# Voltage_Regulators.net
KiCad netlist of a schematic drawn in Altium Designer
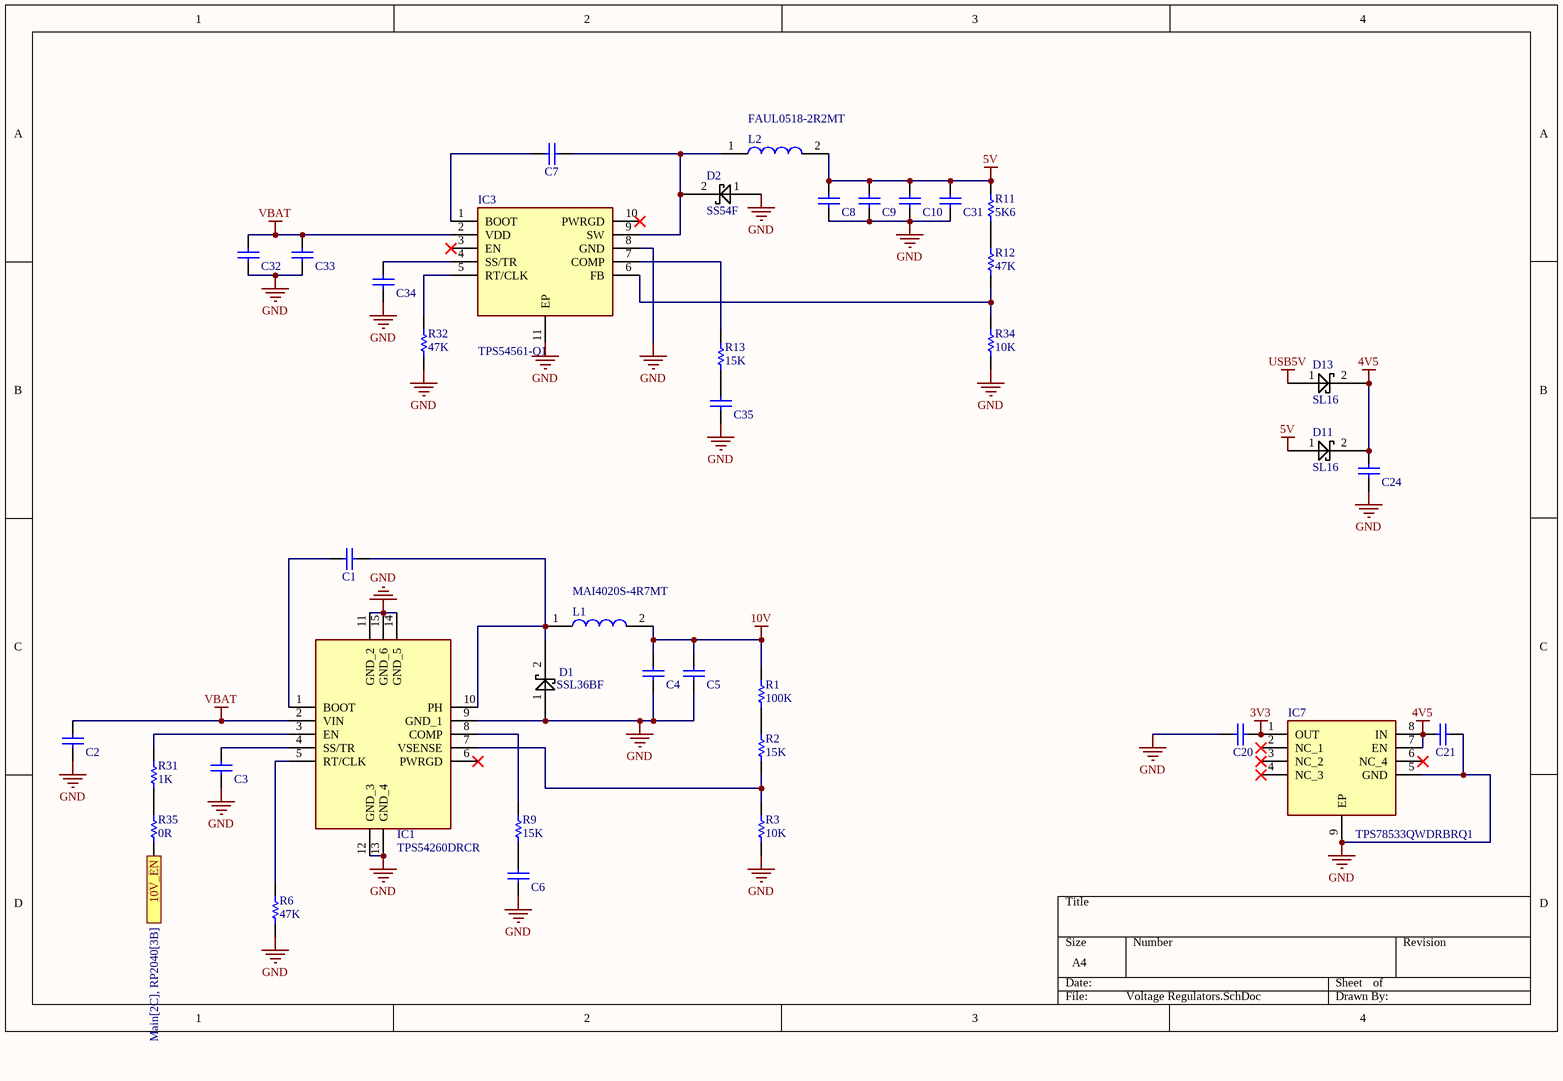
[diagram p0: Voltage Regulators.SchDoc]

(export (version "E")
  (design (tool "Eeschema 10.0.6"))
  (components
    (comp (ref "C1")
      (value "100nF")
      (footprint "WCAP-CSGP_0603_L1.6W0.8H0.8_Reflow")
      (description "WCAP-CSGP Multilayer Ceramic Chip Capacitor, General Purpose, size 0603, X7R, 100nF, 16VDC")
      (fields
        (field (name "MANUFACTURER PART NUMBER") "885012206046")
        (field (name "MANUFACTURER") "Wurth Elektronik")
      )
      (libsource (lib "Altium_WCAP-CSGP (rev22e)") (part "885012206046"))
    )
    (comp (ref "C2")
      (value "3.3µF")
      (footprint "WCAP-CSGP_1206_L3.2W1.6H1.6")
      (description "TDK C3216X7S2A335KT000N\r\n3.3µF MLCC 1206 100V X7S")
      (fields
        (field (name "MANUFACTURER PART NUMBER") "885012208124")
        (field (name "MANUFACTURER") "Wurth Elektronik")
      )
      (libsource (lib "Altium_WCAP-CSGP (rev22e)") (part "885012208124"))
    )
    (comp (ref "C3")
      (value "10nF")
      (footprint "WCAP-CSGP_0603_L1.6W0.8H0.8_Reflow")
      (description "WCAP-CSGP Multilayer Ceramic Chip Capacitor, General Purpose, size 0603, X7R, 10nF, 16VDC")
      (fields
        (field (name "MANUFACTURER PART NUMBER") "885012206040")
        (field (name "MANUFACTURER") "Wurth Elektronik")
      )
      (libsource (lib "Altium_WCAP-CSGP (rev22e)") (part "885012206040"))
    )
    (comp (ref "C4")
      (value "4.7µF")
      (footprint "WCAP-CSGP_0805_L2W1.25H1.25")
      (description "CL21A475KAQNNNG")
      (fields
        (field (name "MANUFACTURER PART NUMBER") "885012107013")
        (field (name "MANUFACTURER") "Wurth Elektronik")
      )
      (libsource (lib "Altium_WCAP-CSGP (rev22e)") (part "885012107013"))
    )
    (comp (ref "C5")
      (value "4.7µF")
      (footprint "WCAP-CSGP_0805_L2W1.25H1.25")
      (description "CL21A475KAQNNNG")
      (fields
        (field (name "MANUFACTURER PART NUMBER") "885012107013")
        (field (name "MANUFACTURER") "Wurth Elektronik")
      )
      (libsource (lib "Altium_WCAP-CSGP (rev22e)") (part "885012107013"))
    )
    (comp (ref "C6")
      (value "2.5pF")
      (footprint "WCAP-CSGP_0603_L1.6W0.8H0.8_Reflow")
      (description "TCC0603COG2R5C500CT")
      (fields
        (field (name "MANUFACTURER PART NUMBER") "885012006030")
        (field (name "MANUFACTURER") "Wurth Elektronik")
      )
      (libsource (lib "Altium_WCAP-CSGP (rev22e)") (part "885012006030"))
    )
    (comp (ref "C7")
      (value "100nF")
      (footprint "WCAP-CSGP_0603_L1.6W0.8H0.8_Reflow")
      (description "WCAP-CSGP Multilayer Ceramic Chip Capacitor, General Purpose, size 0603, X7R, 100nF, 16VDC")
      (fields
        (field (name "MANUFACTURER PART NUMBER") "885012206046")
        (field (name "MANUFACTURER") "Wurth Elektronik")
      )
      (libsource (lib "Altium_WCAP-CSGP (rev22e)") (part "885012206046"))
    )
    (comp (ref "C8")
      (value "4.7µF")
      (footprint "WCAP-CSGP_0805_L2W1.25H1.25")
      (description "CL21A475KAQNNNG")
      (fields
        (field (name "MANUFACTURER PART NUMBER") "885012107013")
        (field (name "MANUFACTURER") "Wurth Elektronik")
      )
      (libsource (lib "Altium_WCAP-CSGP (rev22e)") (part "885012107013"))
    )
    (comp (ref "C9")
      (value "4.7µF")
      (footprint "WCAP-CSGP_0805_L2W1.25H1.25")
      (description "CL21A475KAQNNNG")
      (fields
        (field (name "MANUFACTURER PART NUMBER") "885012107013")
        (field (name "MANUFACTURER") "Wurth Elektronik")
      )
      (libsource (lib "Altium_WCAP-CSGP (rev22e)") (part "885012107013"))
    )
    (comp (ref "C10")
      (value "4.7µF")
      (footprint "WCAP-CSGP_0805_L2W1.25H1.25")
      (description "CL21A475KAQNNNG")
      (fields
        (field (name "MANUFACTURER PART NUMBER") "885012107013")
        (field (name "MANUFACTURER") "Wurth Elektronik")
      )
      (libsource (lib "Altium_WCAP-CSGP (rev22e)") (part "885012107013"))
    )
    (comp (ref "C20")
      (value "1µF")
      (footprint "WCAP-CSGP_0603_L1.6W0.8H0.8_Reflow")
      (description "WCAP-CSGP Multilayer Ceramic Chip Capacitor, General Purpose, size 0603, X7R, 1µF, 10VDC")
      (fields
        (field (name "MANUFACTURER PART NUMBER") "885012206026")
        (field (name "MANUFACTURER") "Wurth Elektronik")
      )
      (libsource (lib "Altium_WCAP-CSGP (rev22e)") (part "885012206026"))
    )
    (comp (ref "C21")
      (value "1µF")
      (footprint "WCAP-CSGP_0603_L1.6W0.8H0.8_Reflow")
      (description "WCAP-CSGP Multilayer Ceramic Chip Capacitor, General Purpose, size 0603, X7R, 1µF, 10VDC")
      (fields
        (field (name "MANUFACTURER PART NUMBER") "885012206026")
        (field (name "MANUFACTURER") "Wurth Elektronik")
      )
      (libsource (lib "Altium_WCAP-CSGP (rev22e)") (part "885012206026"))
    )
    (comp (ref "C24")
      (value "1µF")
      (footprint "WCAP-CSGP_0603_L1.6W0.8H0.8_Reflow")
      (description "WCAP-CSGP Multilayer Ceramic Chip Capacitor, General Purpose, size 0603, X5R, 1µF, 16VDC")
      (fields
        (field (name "MANUFACTURER PART NUMBER") "885012106017")
        (field (name "MANUFACTURER") "Wurth Elektronik")
      )
      (libsource (lib "Altium_WCAP-CSGP (rev22e)") (part "885012106017"))
    )
    (comp (ref "C31")
      (value "4.7µF")
      (footprint "WCAP-CSGP_0805_L2W1.25H1.25")
      (description "CL21A475KAQNNNG")
      (fields
        (field (name "MANUFACTURER PART NUMBER") "885012107013")
        (field (name "MANUFACTURER") "Wurth Elektronik")
      )
      (libsource (lib "Altium_WCAP-CSGP (rev22e)") (part "885012107013"))
    )
    (comp (ref "C32")
      (value "2.2µF")
      (footprint "WCAP-CSGP_0805_L2W1.25H1.25")
      (description "CL21B225KBYNNNE")
      (fields
        (field (name "MANUFACTURER PART NUMBER") "885012107013")
        (field (name "MANUFACTURER") "Wurth Elektronik")
      )
      (libsource (lib "Altium_WCAP-CSGP (rev22e)") (part "885012107013"))
    )
    (comp (ref "C33")
      (value "2.2µF")
      (footprint "WCAP-CSGP_0805_L2W1.25H1.25")
      (description "CL21B225KBYNNNE")
      (fields
        (field (name "MANUFACTURER PART NUMBER") "885012107013")
        (field (name "MANUFACTURER") "Wurth Elektronik")
      )
      (libsource (lib "Altium_WCAP-CSGP (rev22e)") (part "885012107013"))
    )
    (comp (ref "C34")
      (value "10nF")
      (footprint "WCAP-CSGP_0603_L1.6W0.8H0.8_Reflow")
      (description "WCAP-CSGP Multilayer Ceramic Chip Capacitor, General Purpose, size 0603, X7R, 10nF, 16VDC")
      (fields
        (field (name "MANUFACTURER PART NUMBER") "885012206040")
        (field (name "MANUFACTURER") "Wurth Elektronik")
      )
      (libsource (lib "Altium_WCAP-CSGP (rev22e)") (part "885012206040"))
    )
    (comp (ref "C35")
      (value "1nF")
      (footprint "WCAP-CSGP_0603_L1.6W0.8H0.8_Reflow")
      (description "TCC0603COG2R5C500CT")
      (fields
        (field (name "MANUFACTURER PART NUMBER") "885012006030")
        (field (name "MANUFACTURER") "Wurth Elektronik")
      )
      (libsource (lib "Altium_WCAP-CSGP (rev22e)") (part "885012006030"))
    )
    (comp (ref "D1")
      (value "SSL36BF")
      (footprint "SSL36BF")
      (libsource (lib "Custom Components") (part "SSL36BF"))
    )
    (comp (ref "D2") (value "SS54F") (footprint "SS54F") (libsource (lib "Custom Components") (part "SS54F")))
    (comp (ref "D11") (value "SL16") (footprint "SL16") (libsource (lib "Custom Components") (part "SL16")))
    (comp (ref "D13") (value "SL16") (footprint "SL16") (libsource (lib "Custom Components") (part "SL16")))
    (comp (ref "IC1")
      (value "TPS54260DRCR")
      (footprint "Custom Components:TPS54040ADRCT")
      (description "Integrated Circuit")
      (fields (field (name "MOUSER PART NUMBER") "595-TPS54260DRCR"))
      (libsource (lib "*") (part "TPS54260DRCR"))
    )
    (comp (ref "IC3")
      (value "TPS54561-Q1")
      (footprint "Custom Components:SON80P400X400X80-11N")
      (description "Integrated Circuit")
      (libsource (lib "*") (part "TPS54561-Q1"))
    )
    (comp (ref "IC7")
      (value "TPS78533QWDRBRQ1")
      (footprint "Custom Components:SON65P300X300X100-9N-D")
      (description "Integrated Circuit")
      (fields (field (name "MOUSER PART NUMBER") "595-TPS78533QWDRBRQ1"))
      (libsource (lib "*") (part "TPS78533QWDRBRQ1"))
    )
    (comp (ref "L1")
      (value "MAI4020S-4R7MT")
      (footprint "MAI4020S-4R7MT")
      (libsource (lib "Custom Components") (part "MAI4020S-4R7MT"))
    )
    (comp (ref "L2")
      (value "FAUL0518-2R2MT")
      (footprint "FAUL0518-2R2MT")
      (libsource (lib "Custom Components") (part "FAUL0518-2R2MT"))
    )
    (comp (ref "R1")
      (value "100K")
      (footprint "RESC0603(1608)_N")
      (description "Chipwiderstand, SMD, Baureihe MC, 1%")
      (fields (field (name "MANUFACTURER") "Multicomp"))
      (libsource (lib "Standardbauteile") (part "Res 100K"))
    )
    (comp (ref "R2")
      (value "15K")
      (footprint "RESC0603(1608)_N")
      (description "Chipwiderstand, SMD, Baureihe MC, 1%")
      (fields (field (name "MANUFACTURER") "Multicomp"))
      (libsource (lib "Standardbauteile") (part "Res 12K"))
    )
    (comp (ref "R3")
      (value "10K")
      (footprint "RESC0603(1608)_N")
      (description "Chipwiderstand, SMD, Baureihe MC, 1%")
      (fields (field (name "MANUFACTURER") "Multicomp"))
      (libsource (lib "Standardbauteile") (part "Res 10K"))
    )
    (comp (ref "R6")
      (value "47K")
      (footprint "RESC0603(1608)_N")
      (description "Chipwiderstand, SMD, Baureihe MC, 1%")
      (fields (field (name "MANUFACTURER") "Multicomp"))
      (libsource (lib "Standardbauteile") (part "Res 47R"))
    )
    (comp (ref "R9")
      (value "15K")
      (footprint "RESC0603(1608)_N")
      (description "Chipwiderstand, SMD, Baureihe MC, 1%")
      (fields (field (name "MANUFACTURER") "Multicomp"))
      (libsource (lib "Standardbauteile") (part "Res 12K"))
    )
    (comp (ref "R11")
      (value "5K6")
      (footprint "RESC0603(1608)_N")
      (description "Chipwiderstand, SMD, Baureihe MC, 1%")
      (fields (field (name "MANUFACTURER") "Multicomp"))
      (libsource (lib "Standardbauteile") (part "Res 100K"))
    )
    (comp (ref "R12")
      (value "47K")
      (footprint "RESC0603(1608)_N")
      (description "Chipwiderstand, SMD, Baureihe MC, 1%")
      (fields (field (name "MANUFACTURER") "Multicomp"))
      (libsource (lib "Standardbauteile") (part "Res 12K"))
    )
    (comp (ref "R13")
      (value "15K")
      (footprint "RESC0603(1608)_N")
      (description "Chipwiderstand, SMD, Baureihe MC, 1%")
      (fields (field (name "MANUFACTURER") "Multicomp"))
      (libsource (lib "Standardbauteile") (part "Res 12K"))
    )
    (comp (ref "R31")
      (value "1K")
      (footprint "RESC0603(1608)_N")
      (description "Chipwiderstand, SMD, Baureihe MC, 1%")
      (fields (field (name "MANUFACTURER") "Multicomp"))
      (libsource (lib "Standardbauteile") (part "Res 1K"))
    )
    (comp (ref "R32")
      (value "47K")
      (footprint "RESC0603(1608)_N")
      (description "Chipwiderstand, SMD, Baureihe MC, 1%")
      (fields (field (name "MANUFACTURER") "Multicomp"))
      (libsource (lib "Standardbauteile") (part "Res 47R"))
    )
    (comp (ref "R34")
      (value "10K")
      (footprint "RESC0603(1608)_N")
      (description "Chipwiderstand, SMD, Baureihe MC, 1%")
      (fields (field (name "MANUFACTURER") "Multicomp"))
      (libsource (lib "Standardbauteile") (part "Res 10K"))
    )
    (comp (ref "R35")
      (value "0R")
      (footprint "RESC0603(1608)_N")
      (description "Chipwiderstand, SMD, Baureihe MC, 1%")
      (fields (field (name "MANUFACTURER") "Multicomp"))
      (libsource (lib "Standardbauteile") (part "Res 0R"))
    )
  )
  (nets
    (net (code "1") (name "/10V_EN") (class "Default")
      (node (ref "R35") (pin "1") (pinfunction "1_1") (pintype "passive"))
    )
    (net (code "2") (name "3V3") (class "Default")
      (node (ref "C20") (pin "2") (pinfunction "2_2") (pintype "passive"))
      (node (ref "IC7") (pin "1") (pinfunction "OUT_1") (pintype "passive"))
    )
    (net (code "3") (name "4V5") (class "Default")
      (node (ref "C21") (pin "1") (pinfunction "1_1") (pintype "passive"))
      (node (ref "C24") (pin "2") (pinfunction "2_2") (pintype "passive"))
      (node (ref "D11") (pin "2") (pinfunction "6_2") (pintype "passive"))
      (node (ref "D13") (pin "2") (pinfunction "6_2") (pintype "passive"))
      (node (ref "IC7") (pin "7") (pinfunction "EN_7") (pintype "passive"))
      (node (ref "IC7") (pin "8") (pinfunction "IN_8") (pintype "passive"))
    )
    (net (code "4") (name "5V") (class "Default")
      (node (ref "C10") (pin "2") (pinfunction "2_2") (pintype "passive"))
      (node (ref "C31") (pin "2") (pinfunction "2_2") (pintype "passive"))
      (node (ref "C8") (pin "2") (pinfunction "2_2") (pintype "passive"))
      (node (ref "C9") (pin "2") (pinfunction "2_2") (pintype "passive"))
      (node (ref "D11") (pin "1") (pinfunction "5_1") (pintype "passive"))
      (node (ref "L2") (pin "2") (pinfunction "2_2") (pintype "passive"))
      (node (ref "R11") (pin "2") (pinfunction "2_2") (pintype "passive"))
    )
    (net (code "5") (name "10V") (class "Default")
      (node (ref "C4") (pin "2") (pinfunction "2_2") (pintype "passive"))
      (node (ref "C5") (pin "2") (pinfunction "2_2") (pintype "passive"))
      (node (ref "L1") (pin "2") (pinfunction "2_2") (pintype "passive"))
      (node (ref "R1") (pin "2") (pinfunction "2_2") (pintype "passive"))
    )
    (net (code "6") (name "GND") (class "Default")
      (node (ref "C10") (pin "1") (pinfunction "1_1") (pintype "passive"))
      (node (ref "C2") (pin "1") (pinfunction "1_1") (pintype "passive"))
      (node (ref "C20") (pin "1") (pinfunction "1_1") (pintype "passive"))
      (node (ref "C21") (pin "2") (pinfunction "2_2") (pintype "passive"))
      (node (ref "C24") (pin "1") (pinfunction "1_1") (pintype "passive"))
      (node (ref "C3") (pin "1") (pinfunction "1_1") (pintype "passive"))
      (node (ref "C31") (pin "1") (pinfunction "1_1") (pintype "passive"))
      (node (ref "C32") (pin "1") (pinfunction "1_1") (pintype "passive"))
      (node (ref "C33") (pin "1") (pinfunction "1_1") (pintype "passive"))
      (node (ref "C34") (pin "1") (pinfunction "1_1") (pintype "passive"))
      (node (ref "C35") (pin "1") (pinfunction "1_1") (pintype "passive"))
      (node (ref "C4") (pin "1") (pinfunction "1_1") (pintype "passive"))
      (node (ref "C5") (pin "1") (pinfunction "1_1") (pintype "passive"))
      (node (ref "C6") (pin "1") (pinfunction "1_1") (pintype "passive"))
      (node (ref "C8") (pin "1") (pinfunction "1_1") (pintype "passive"))
      (node (ref "C9") (pin "1") (pinfunction "1_1") (pintype "passive"))
      (node (ref "D1") (pin "1") (pinfunction "5_1") (pintype "passive"))
      (node (ref "D2") (pin "1") (pinfunction "5_1") (pintype "passive"))
      (node (ref "IC1") (pin "11") (pinfunction "GND_2_11") (pintype "passive"))
      (node (ref "IC1") (pin "12") (pinfunction "GND_3_12") (pintype "passive"))
      (node (ref "IC1") (pin "13") (pinfunction "GND_4_13") (pintype "passive"))
      (node (ref "IC1") (pin "14") (pinfunction "GND_5_14") (pintype "passive"))
      (node (ref "IC1") (pin "15") (pinfunction "GND_6_15") (pintype "passive"))
      (node (ref "IC1") (pin "9") (pinfunction "GND_1_9") (pintype "passive"))
      (node (ref "IC3") (pin "11") (pinfunction "EP_11") (pintype "passive"))
      (node (ref "IC3") (pin "8") (pinfunction "GND_8") (pintype "passive"))
      (node (ref "IC7") (pin "5") (pinfunction "GND_5") (pintype "passive"))
      (node (ref "IC7") (pin "9") (pinfunction "EP_9") (pintype "passive"))
      (node (ref "R3") (pin "1") (pinfunction "1_1") (pintype "passive"))
      (node (ref "R32") (pin "1") (pinfunction "1_1") (pintype "passive"))
      (node (ref "R34") (pin "1") (pinfunction "1_1") (pintype "passive"))
      (node (ref "R6") (pin "1") (pinfunction "1_1") (pintype "passive"))
    )
    (net (code "7") (name "Net-(C6-Pad2)") (class "Default")
      (node (ref "C6") (pin "2") (pinfunction "2_2") (pintype "passive"))
      (node (ref "R9") (pin "1") (pinfunction "1_1") (pintype "passive"))
    )
    (net (code "8") (name "Net-(C35-Pad2)") (class "Default")
      (node (ref "C35") (pin "2") (pinfunction "2_2") (pintype "passive"))
      (node (ref "R13") (pin "1") (pinfunction "1_1") (pintype "passive"))
    )
    (net (code "9") (name "Net-(D1-6)") (class "Default")
      (node (ref "C1") (pin "2") (pinfunction "2_2") (pintype "passive"))
      (node (ref "D1") (pin "2") (pinfunction "6_2") (pintype "passive"))
      (node (ref "IC1") (pin "10") (pinfunction "PH_10") (pintype "passive"))
      (node (ref "L1") (pin "1") (pinfunction "1_1") (pintype "passive"))
    )
    (net (code "10") (name "Net-(D2-6)") (class "Default")
      (node (ref "C7") (pin "2") (pinfunction "2_2") (pintype "passive"))
      (node (ref "D2") (pin "2") (pinfunction "6_2") (pintype "passive"))
      (node (ref "IC3") (pin "9") (pinfunction "SW_9") (pintype "passive"))
      (node (ref "L2") (pin "1") (pinfunction "1_1") (pintype "passive"))
    )
    (net (code "11") (name "Net-(IC1-BOOT)") (class "Default")
      (node (ref "C1") (pin "1") (pinfunction "1_1") (pintype "passive"))
      (node (ref "IC1") (pin "1") (pinfunction "BOOT_1") (pintype "passive"))
    )
    (net (code "12") (name "Net-(IC1-COMP)") (class "Default")
      (node (ref "IC1") (pin "8") (pinfunction "COMP_8") (pintype "passive"))
      (node (ref "R9") (pin "2") (pinfunction "2_2") (pintype "passive"))
    )
    (net (code "13") (name "Net-(IC1-EN)") (class "Default")
      (node (ref "IC1") (pin "3") (pinfunction "EN_3") (pintype "passive"))
      (node (ref "R31") (pin "2") (pinfunction "2_2") (pintype "passive"))
    )
    (net (code "14") (name "Net-(IC1-RT{slash}CLK)") (class "Default")
      (node (ref "IC1") (pin "5") (pinfunction "RT/CLK_5") (pintype "passive"))
      (node (ref "R6") (pin "2") (pinfunction "2_2") (pintype "passive"))
    )
    (net (code "15") (name "Net-(IC1-SS{slash}TR)") (class "Default")
      (node (ref "C3") (pin "2") (pinfunction "2_2") (pintype "passive"))
      (node (ref "IC1") (pin "4") (pinfunction "SS/TR_4") (pintype "passive"))
    )
    (net (code "16") (name "Net-(IC1-VSENSE)") (class "Default")
      (node (ref "IC1") (pin "7") (pinfunction "VSENSE_7") (pintype "passive"))
      (node (ref "R2") (pin "1") (pinfunction "1_1") (pintype "passive"))
      (node (ref "R3") (pin "2") (pinfunction "2_2") (pintype "passive"))
    )
    (net (code "17") (name "Net-(IC3-BOOT)") (class "Default")
      (node (ref "C7") (pin "1") (pinfunction "1_1") (pintype "passive"))
      (node (ref "IC3") (pin "1") (pinfunction "BOOT_1") (pintype "passive"))
    )
    (net (code "18") (name "Net-(IC3-COMP)") (class "Default")
      (node (ref "IC3") (pin "7") (pinfunction "COMP_7") (pintype "passive"))
      (node (ref "R13") (pin "2") (pinfunction "2_2") (pintype "passive"))
    )
    (net (code "19") (name "Net-(IC3-FB)") (class "Default")
      (node (ref "IC3") (pin "6") (pinfunction "FB_6") (pintype "passive"))
      (node (ref "R12") (pin "1") (pinfunction "1_1") (pintype "passive"))
      (node (ref "R34") (pin "2") (pinfunction "2_2") (pintype "passive"))
    )
    (net (code "20") (name "Net-(IC3-RT{slash}CLK)") (class "Default")
      (node (ref "IC3") (pin "5") (pinfunction "RT/CLK_5") (pintype "passive"))
      (node (ref "R32") (pin "2") (pinfunction "2_2") (pintype "passive"))
    )
    (net (code "21") (name "Net-(IC3-SS{slash}TR)") (class "Default")
      (node (ref "C34") (pin "2") (pinfunction "2_2") (pintype "passive"))
      (node (ref "IC3") (pin "4") (pinfunction "SS/TR_4") (pintype "passive"))
    )
    (net (code "22") (name "Net-(R1-Pad1)") (class "Default")
      (node (ref "R1") (pin "1") (pinfunction "1_1") (pintype "passive"))
      (node (ref "R2") (pin "2") (pinfunction "2_2") (pintype "passive"))
    )
    (net (code "23") (name "Net-(R11-Pad1)") (class "Default")
      (node (ref "R11") (pin "1") (pinfunction "1_1") (pintype "passive"))
      (node (ref "R12") (pin "2") (pinfunction "2_2") (pintype "passive"))
    )
    (net (code "24") (name "Net-(R31-Pad1)") (class "Default")
      (node (ref "R31") (pin "1") (pinfunction "1_1") (pintype "passive"))
      (node (ref "R35") (pin "2") (pinfunction "2_2") (pintype "passive"))
    )
    (net (code "25") (name "USB5V") (class "Default")
      (node (ref "D13") (pin "1") (pinfunction "5_1") (pintype "passive"))
    )
    (net (code "26") (name "VBAT") (class "Default")
      (node (ref "C2") (pin "2") (pinfunction "2_2") (pintype "passive"))
      (node (ref "C32") (pin "2") (pinfunction "2_2") (pintype "passive"))
      (node (ref "C33") (pin "2") (pinfunction "2_2") (pintype "passive"))
      (node (ref "IC1") (pin "2") (pinfunction "VIN_2") (pintype "passive"))
      (node (ref "IC3") (pin "2") (pinfunction "VDD_2") (pintype "passive"))
    )
    (net (code "27") (name "unconnected-(IC1-PWRGD-Pad6)") (class "Default")
      (node (ref "IC1") (pin "6") (pinfunction "PWRGD_6") (pintype "passive+no_connect"))
    )
    (net (code "28") (name "unconnected-(IC3-EN-Pad3)") (class "Default")
      (node (ref "IC3") (pin "3") (pinfunction "EN_3") (pintype "passive+no_connect"))
    )
    (net (code "29") (name "unconnected-(IC3-PWRGD-Pad10)") (class "Default")
      (node (ref "IC3") (pin "10") (pinfunction "PWRGD_10") (pintype "passive+no_connect"))
    )
    (net (code "30") (name "unconnected-(IC7-NC_1-Pad2)") (class "Default")
      (node (ref "IC7") (pin "2") (pinfunction "NC_1_2") (pintype "passive+no_connect"))
    )
    (net (code "31") (name "unconnected-(IC7-NC_2-Pad3)") (class "Default")
      (node (ref "IC7") (pin "3") (pinfunction "NC_2_3") (pintype "passive+no_connect"))
    )
    (net (code "32") (name "unconnected-(IC7-NC_3-Pad4)") (class "Default")
      (node (ref "IC7") (pin "4") (pinfunction "NC_3_4") (pintype "passive+no_connect"))
    )
    (net (code "33") (name "unconnected-(IC7-NC_4-Pad6)") (class "Default")
      (node (ref "IC7") (pin "6") (pinfunction "NC_4_6") (pintype "passive+no_connect"))
    )
  )
)
